# PGTNX08_pitch_out.net
KiCad netlist of a schematic drawn in EAGLE
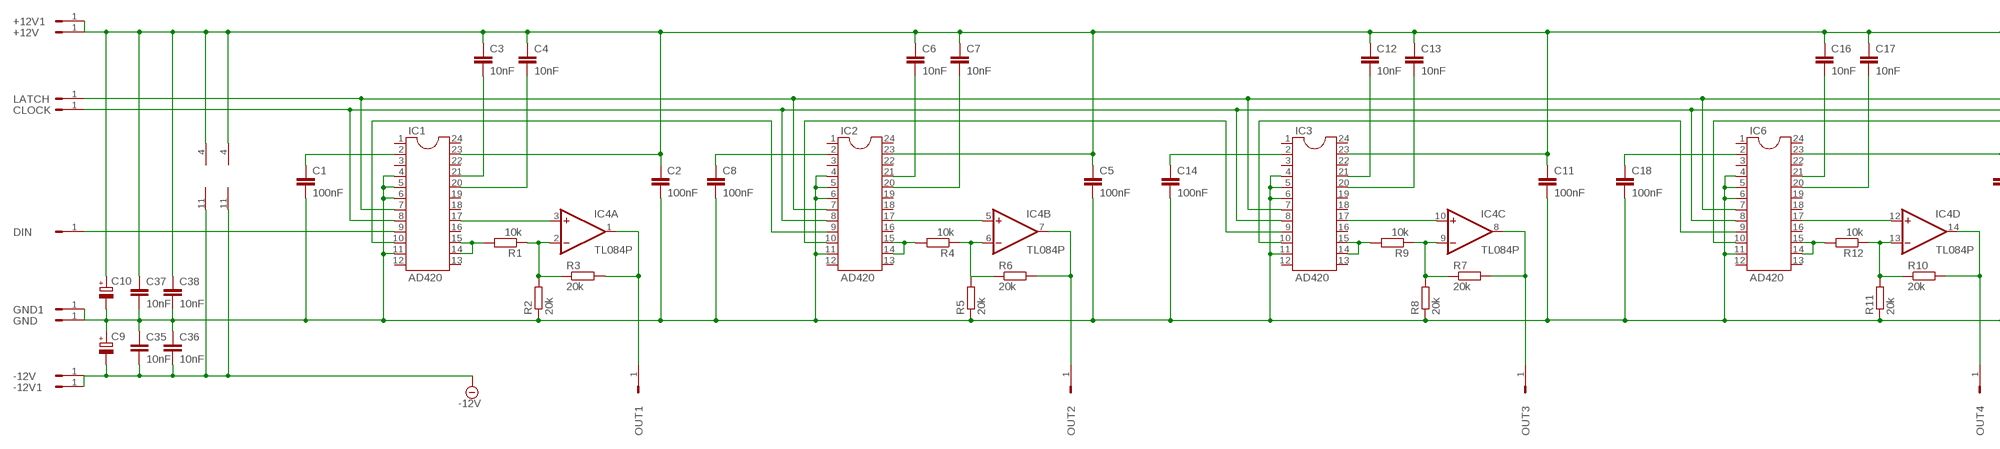
[diagram p0: schematic, sheet 1, part 1 of 2]
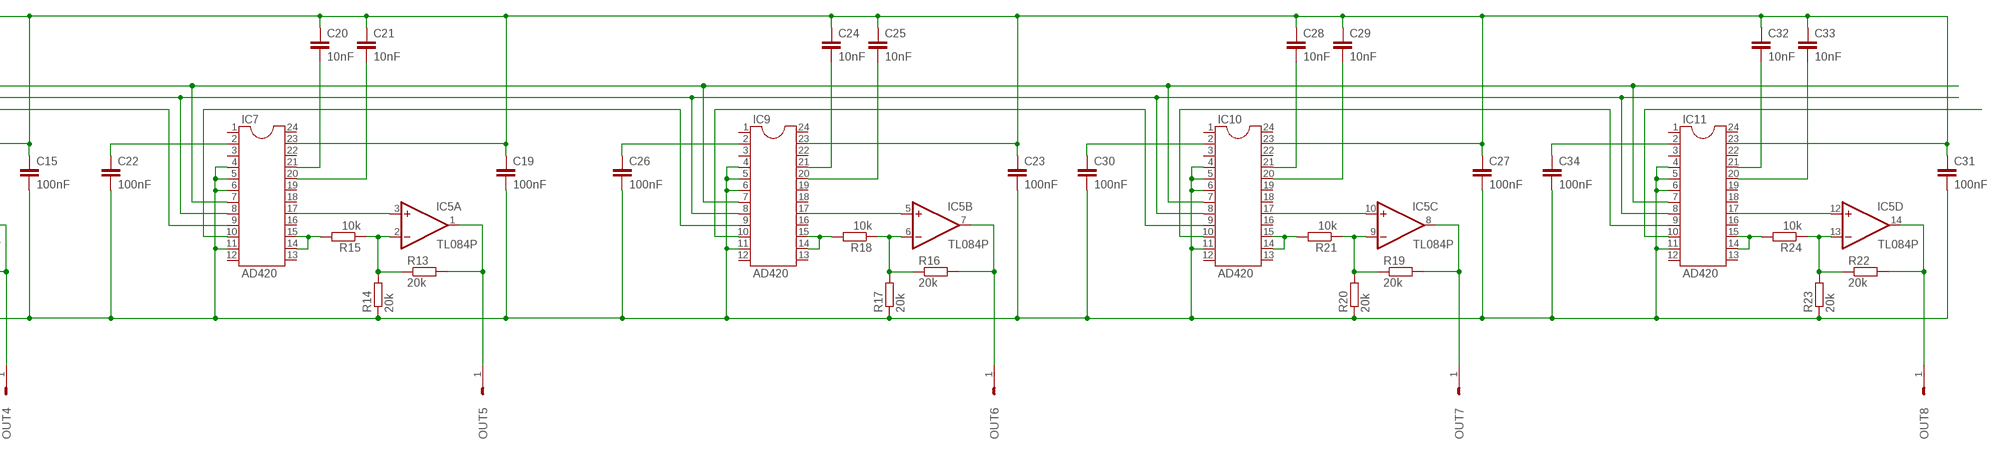
[diagram p1: schematic, sheet 1, part 2 of 2]

(export (version "E")
  (design (tool "Eeschema 10.0.6"))
  (components
    (comp (ref "+12V")
      (value "HEADER/MALE/01")
      (footprint "eagle-import:HEADER_MALE_01")
      (libsource (lib "eagle-import") (part "HEADER/MALE/01"))
    )
    (comp (ref "+12V1")
      (value "HEADER/MALE/01")
      (footprint "eagle-import:HEADER_MALE_01")
      (libsource (lib "eagle-import") (part "HEADER/MALE/01"))
    )
    (comp (ref "-12V")
      (value "HEADER/MALE/01")
      (footprint "eagle-import:HEADER_MALE_01")
      (libsource (lib "eagle-import") (part "HEADER/MALE/01"))
    )
    (comp (ref "-12V1")
      (value "HEADER/MALE/01")
      (footprint "eagle-import:HEADER_MALE_01")
      (libsource (lib "eagle-import") (part "HEADER/MALE/01"))
    )
    (comp (ref "C1")
      (value "100nF")
      (footprint "eagle-import:CERAMICDISC_5")
      (libsource (lib "eagle-import") (part "CAPACITORCERAMICDISC/5"))
    )
    (comp (ref "C2")
      (value "100nF")
      (footprint "eagle-import:CERAMICDISC_5")
      (libsource (lib "eagle-import") (part "CAPACITORCERAMICDISC/5"))
    )
    (comp (ref "C3")
      (value "10nF")
      (footprint "eagle-import:CERAMICDISC_5")
      (libsource (lib "eagle-import") (part "CAPACITORCERAMICDISC/5"))
    )
    (comp (ref "C4")
      (value "10nF")
      (footprint "eagle-import:CERAMICDISC_5")
      (libsource (lib "eagle-import") (part "CAPACITORCERAMICDISC/5"))
    )
    (comp (ref "C5")
      (value "100nF")
      (footprint "eagle-import:CERAMICDISC_5")
      (libsource (lib "eagle-import") (part "CAPACITORCERAMICDISC/5"))
    )
    (comp (ref "C6")
      (value "10nF")
      (footprint "eagle-import:CERAMICDISC_5")
      (libsource (lib "eagle-import") (part "CAPACITORCERAMICDISC/5"))
    )
    (comp (ref "C7")
      (value "10nF")
      (footprint "eagle-import:CERAMICDISC_5")
      (libsource (lib "eagle-import") (part "CAPACITORCERAMICDISC/5"))
    )
    (comp (ref "C8")
      (value "100nF")
      (footprint "eagle-import:CERAMICDISC_5")
      (libsource (lib "eagle-import") (part "CAPACITORCERAMICDISC/5"))
    )
    (comp (ref "C9")
      (value "CAPACITOR/POLARIZEDE2.5-6")
      (footprint "eagle-import:E2,5-6")
      (libsource (lib "eagle-import") (part "CAPACITOR/POLARIZEDE2.5-6"))
    )
    (comp (ref "C10")
      (value "CAPACITOR/POLARIZEDE2.5-6")
      (footprint "eagle-import:E2,5-6")
      (libsource (lib "eagle-import") (part "CAPACITOR/POLARIZEDE2.5-6"))
    )
    (comp (ref "C11")
      (value "100nF")
      (footprint "eagle-import:CERAMICDISC_5")
      (libsource (lib "eagle-import") (part "CAPACITORCERAMICDISC/5"))
    )
    (comp (ref "C12")
      (value "10nF")
      (footprint "eagle-import:CERAMICDISC_5")
      (libsource (lib "eagle-import") (part "CAPACITORCERAMICDISC/5"))
    )
    (comp (ref "C13")
      (value "10nF")
      (footprint "eagle-import:CERAMICDISC_5")
      (libsource (lib "eagle-import") (part "CAPACITORCERAMICDISC/5"))
    )
    (comp (ref "C14")
      (value "100nF")
      (footprint "eagle-import:CERAMICDISC_5")
      (libsource (lib "eagle-import") (part "CAPACITORCERAMICDISC/5"))
    )
    (comp (ref "C15")
      (value "100nF")
      (footprint "eagle-import:CERAMICDISC_5")
      (libsource (lib "eagle-import") (part "CAPACITORCERAMICDISC/5"))
    )
    (comp (ref "C16")
      (value "10nF")
      (footprint "eagle-import:CERAMICDISC_5")
      (libsource (lib "eagle-import") (part "CAPACITORCERAMICDISC/5"))
    )
    (comp (ref "C17")
      (value "10nF")
      (footprint "eagle-import:CERAMICDISC_5")
      (libsource (lib "eagle-import") (part "CAPACITORCERAMICDISC/5"))
    )
    (comp (ref "C18")
      (value "100nF")
      (footprint "eagle-import:CERAMICDISC_5")
      (libsource (lib "eagle-import") (part "CAPACITORCERAMICDISC/5"))
    )
    (comp (ref "C19")
      (value "100nF")
      (footprint "eagle-import:CERAMICDISC_5")
      (libsource (lib "eagle-import") (part "CAPACITORCERAMICDISC/5"))
    )
    (comp (ref "C20")
      (value "10nF")
      (footprint "eagle-import:CERAMICDISC_5")
      (libsource (lib "eagle-import") (part "CAPACITORCERAMICDISC/5"))
    )
    (comp (ref "C21")
      (value "10nF")
      (footprint "eagle-import:CERAMICDISC_5")
      (libsource (lib "eagle-import") (part "CAPACITORCERAMICDISC/5"))
    )
    (comp (ref "C22")
      (value "100nF")
      (footprint "eagle-import:CERAMICDISC_5")
      (libsource (lib "eagle-import") (part "CAPACITORCERAMICDISC/5"))
    )
    (comp (ref "C23")
      (value "100nF")
      (footprint "eagle-import:CERAMICDISC_5")
      (libsource (lib "eagle-import") (part "CAPACITORCERAMICDISC/5"))
    )
    (comp (ref "C24")
      (value "10nF")
      (footprint "eagle-import:CERAMICDISC_5")
      (libsource (lib "eagle-import") (part "CAPACITORCERAMICDISC/5"))
    )
    (comp (ref "C25")
      (value "10nF")
      (footprint "eagle-import:CERAMICDISC_5")
      (libsource (lib "eagle-import") (part "CAPACITORCERAMICDISC/5"))
    )
    (comp (ref "C26")
      (value "100nF")
      (footprint "eagle-import:CERAMICDISC_5")
      (libsource (lib "eagle-import") (part "CAPACITORCERAMICDISC/5"))
    )
    (comp (ref "C27")
      (value "100nF")
      (footprint "eagle-import:CERAMICDISC_5")
      (libsource (lib "eagle-import") (part "CAPACITORCERAMICDISC/5"))
    )
    (comp (ref "C28")
      (value "10nF")
      (footprint "eagle-import:CERAMICDISC_5")
      (libsource (lib "eagle-import") (part "CAPACITORCERAMICDISC/5"))
    )
    (comp (ref "C29")
      (value "10nF")
      (footprint "eagle-import:CERAMICDISC_5")
      (libsource (lib "eagle-import") (part "CAPACITORCERAMICDISC/5"))
    )
    (comp (ref "C30")
      (value "100nF")
      (footprint "eagle-import:CERAMICDISC_5")
      (libsource (lib "eagle-import") (part "CAPACITORCERAMICDISC/5"))
    )
    (comp (ref "C31")
      (value "100nF")
      (footprint "eagle-import:CERAMICDISC_5")
      (libsource (lib "eagle-import") (part "CAPACITORCERAMICDISC/5"))
    )
    (comp (ref "C32")
      (value "10nF")
      (footprint "eagle-import:CERAMICDISC_5")
      (libsource (lib "eagle-import") (part "CAPACITORCERAMICDISC/5"))
    )
    (comp (ref "C33")
      (value "10nF")
      (footprint "eagle-import:CERAMICDISC_5")
      (libsource (lib "eagle-import") (part "CAPACITORCERAMICDISC/5"))
    )
    (comp (ref "C34")
      (value "100nF")
      (footprint "eagle-import:CERAMICDISC_5")
      (libsource (lib "eagle-import") (part "CAPACITORCERAMICDISC/5"))
    )
    (comp (ref "C35")
      (value "10nF")
      (footprint "eagle-import:CERAMICDISC_5")
      (libsource (lib "eagle-import") (part "CAPACITORCERAMICDISC/5"))
    )
    (comp (ref "C36")
      (value "10nF")
      (footprint "eagle-import:CERAMICDISC_5")
      (libsource (lib "eagle-import") (part "CAPACITORCERAMICDISC/5"))
    )
    (comp (ref "C37")
      (value "10nF")
      (footprint "eagle-import:CERAMICDISC_5")
      (libsource (lib "eagle-import") (part "CAPACITORCERAMICDISC/5"))
    )
    (comp (ref "C38")
      (value "10nF")
      (footprint "eagle-import:CERAMICDISC_5")
      (libsource (lib "eagle-import") (part "CAPACITORCERAMICDISC/5"))
    )
    (comp (ref "CLOCK")
      (value "HEADER/MALE/01")
      (footprint "eagle-import:HEADER_MALE_01")
      (libsource (lib "eagle-import") (part "HEADER/MALE/01"))
    )
    (comp (ref "DIN")
      (value "HEADER/MALE/01")
      (footprint "eagle-import:HEADER_MALE_01")
      (libsource (lib "eagle-import") (part "HEADER/MALE/01"))
    )
    (comp (ref "GND")
      (value "HEADER/MALE/01")
      (footprint "eagle-import:HEADER_MALE_01")
      (libsource (lib "eagle-import") (part "HEADER/MALE/01"))
    )
    (comp (ref "GND1")
      (value "HEADER/MALE/01")
      (footprint "eagle-import:HEADER_MALE_01")
      (libsource (lib "eagle-import") (part "HEADER/MALE/01"))
    )
    (comp (ref "IC1")
      (value "AD420")
      (footprint "eagle-import:DIL24-3")
      (libsource (lib "eagle-import") (part "DIL24-3"))
    )
    (comp (ref "IC2")
      (value "AD420")
      (footprint "eagle-import:DIL24-3")
      (libsource (lib "eagle-import") (part "DIL24-3"))
    )
    (comp (ref "IC3")
      (value "AD420")
      (footprint "eagle-import:DIL24-3")
      (libsource (lib "eagle-import") (part "DIL24-3"))
    )
    (comp (ref "IC4")
      (value "TL084P")
      (footprint "eagle-import:DIL14")
      (libsource (lib "eagle-import") (part "TL084P"))
    )
    (comp (ref "IC5")
      (value "TL084P")
      (footprint "eagle-import:DIL14")
      (libsource (lib "eagle-import") (part "TL084P"))
    )
    (comp (ref "IC6")
      (value "AD420")
      (footprint "eagle-import:DIL24-3")
      (libsource (lib "eagle-import") (part "DIL24-3"))
    )
    (comp (ref "IC7")
      (value "AD420")
      (footprint "eagle-import:DIL24-3")
      (libsource (lib "eagle-import") (part "DIL24-3"))
    )
    (comp (ref "IC9")
      (value "AD420")
      (footprint "eagle-import:DIL24-3")
      (libsource (lib "eagle-import") (part "DIL24-3"))
    )
    (comp (ref "IC10")
      (value "AD420")
      (footprint "eagle-import:DIL24-3")
      (libsource (lib "eagle-import") (part "DIL24-3"))
    )
    (comp (ref "IC11")
      (value "AD420")
      (footprint "eagle-import:DIL24-3")
      (libsource (lib "eagle-import") (part "DIL24-3"))
    )
    (comp (ref "LATCH")
      (value "HEADER/MALE/01")
      (footprint "eagle-import:HEADER_MALE_01")
      (libsource (lib "eagle-import") (part "HEADER/MALE/01"))
    )
    (comp (ref "OUT1")
      (value "HEADER/MALE/01")
      (footprint "eagle-import:HEADER_MALE_01")
      (libsource (lib "eagle-import") (part "HEADER/MALE/01"))
    )
    (comp (ref "OUT2")
      (value "HEADER/MALE/01")
      (footprint "eagle-import:HEADER_MALE_01")
      (libsource (lib "eagle-import") (part "HEADER/MALE/01"))
    )
    (comp (ref "OUT3")
      (value "HEADER/MALE/01")
      (footprint "eagle-import:HEADER_MALE_01")
      (libsource (lib "eagle-import") (part "HEADER/MALE/01"))
    )
    (comp (ref "OUT4")
      (value "HEADER/MALE/01")
      (footprint "eagle-import:HEADER_MALE_01")
      (libsource (lib "eagle-import") (part "HEADER/MALE/01"))
    )
    (comp (ref "OUT5")
      (value "HEADER/MALE/01")
      (footprint "eagle-import:HEADER_MALE_01")
      (libsource (lib "eagle-import") (part "HEADER/MALE/01"))
    )
    (comp (ref "OUT6")
      (value "HEADER/MALE/01")
      (footprint "eagle-import:HEADER_MALE_01")
      (libsource (lib "eagle-import") (part "HEADER/MALE/01"))
    )
    (comp (ref "OUT7")
      (value "HEADER/MALE/01")
      (footprint "eagle-import:HEADER_MALE_01")
      (libsource (lib "eagle-import") (part "HEADER/MALE/01"))
    )
    (comp (ref "OUT8")
      (value "HEADER/MALE/01")
      (footprint "eagle-import:HEADER_MALE_01")
      (libsource (lib "eagle-import") (part "HEADER/MALE/01"))
    )
    (comp (ref "R1")
      (value "10k")
      (footprint "eagle-import:0204_7")
      (libsource (lib "eagle-import") (part "R-EU_0204/7"))
    )
    (comp (ref "R2")
      (value "20k")
      (footprint "eagle-import:0204_7")
      (libsource (lib "eagle-import") (part "R-EU_0204/7"))
    )
    (comp (ref "R3")
      (value "20k")
      (footprint "eagle-import:RESISTOR_7.5")
      (libsource (lib "eagle-import") (part "RESISTORRESISTOR/UPRIGHT/7.5"))
    )
    (comp (ref "R4")
      (value "10k")
      (footprint "eagle-import:0204_7")
      (libsource (lib "eagle-import") (part "R-EU_0204/7"))
    )
    (comp (ref "R5")
      (value "20k")
      (footprint "eagle-import:0204_7")
      (libsource (lib "eagle-import") (part "R-EU_0204/7"))
    )
    (comp (ref "R6")
      (value "20k")
      (footprint "eagle-import:RESISTOR_7.5")
      (libsource (lib "eagle-import") (part "RESISTORRESISTOR/UPRIGHT/7.5"))
    )
    (comp (ref "R7")
      (value "20k")
      (footprint "eagle-import:RESISTOR_7.5")
      (libsource (lib "eagle-import") (part "RESISTORRESISTOR/UPRIGHT/7.5"))
    )
    (comp (ref "R8")
      (value "20k")
      (footprint "eagle-import:RESISTOR_7.5")
      (libsource (lib "eagle-import") (part "RESISTORRESISTOR/UPRIGHT/7.5"))
    )
    (comp (ref "R9")
      (value "10k")
      (footprint "eagle-import:RESISTOR_7.5")
      (libsource (lib "eagle-import") (part "RESISTORRESISTOR/UPRIGHT/7.5"))
    )
    (comp (ref "R10")
      (value "20k")
      (footprint "eagle-import:RESISTOR_7.5")
      (libsource (lib "eagle-import") (part "RESISTORRESISTOR/UPRIGHT/7.5"))
    )
    (comp (ref "R11")
      (value "20k")
      (footprint "eagle-import:RESISTOR_7.5")
      (libsource (lib "eagle-import") (part "RESISTORRESISTOR/UPRIGHT/7.5"))
    )
    (comp (ref "R12")
      (value "10k")
      (footprint "eagle-import:RESISTOR_7.5")
      (libsource (lib "eagle-import") (part "RESISTORRESISTOR/UPRIGHT/7.5"))
    )
    (comp (ref "R13")
      (value "20k")
      (footprint "eagle-import:RESISTOR_7.5")
      (libsource (lib "eagle-import") (part "RESISTORRESISTOR/UPRIGHT/7.5"))
    )
    (comp (ref "R14")
      (value "20k")
      (footprint "eagle-import:RESISTOR_7.5")
      (libsource (lib "eagle-import") (part "RESISTORRESISTOR/UPRIGHT/7.5"))
    )
    (comp (ref "R15")
      (value "10k")
      (footprint "eagle-import:RESISTOR_7.5")
      (libsource (lib "eagle-import") (part "RESISTORRESISTOR/UPRIGHT/7.5"))
    )
    (comp (ref "R16")
      (value "20k")
      (footprint "eagle-import:RESISTOR_7.5")
      (libsource (lib "eagle-import") (part "RESISTORRESISTOR/UPRIGHT/7.5"))
    )
    (comp (ref "R17")
      (value "20k")
      (footprint "eagle-import:RESISTOR_7.5")
      (libsource (lib "eagle-import") (part "RESISTORRESISTOR/UPRIGHT/7.5"))
    )
    (comp (ref "R18")
      (value "10k")
      (footprint "eagle-import:RESISTOR_7.5")
      (libsource (lib "eagle-import") (part "RESISTORRESISTOR/UPRIGHT/7.5"))
    )
    (comp (ref "R19")
      (value "20k")
      (footprint "eagle-import:RESISTOR_7.5")
      (libsource (lib "eagle-import") (part "RESISTORRESISTOR/UPRIGHT/7.5"))
    )
    (comp (ref "R20")
      (value "20k")
      (footprint "eagle-import:RESISTOR_7.5")
      (libsource (lib "eagle-import") (part "RESISTORRESISTOR/UPRIGHT/7.5"))
    )
    (comp (ref "R21")
      (value "10k")
      (footprint "eagle-import:RESISTOR_7.5")
      (libsource (lib "eagle-import") (part "RESISTORRESISTOR/UPRIGHT/7.5"))
    )
    (comp (ref "R22")
      (value "20k")
      (footprint "eagle-import:RESISTOR_7.5")
      (libsource (lib "eagle-import") (part "RESISTORRESISTOR/UPRIGHT/7.5"))
    )
    (comp (ref "R23")
      (value "20k")
      (footprint "eagle-import:RESISTOR_7.5")
      (libsource (lib "eagle-import") (part "RESISTORRESISTOR/UPRIGHT/7.5"))
    )
    (comp (ref "R24")
      (value "10k")
      (footprint "eagle-import:RESISTOR_7.5")
      (libsource (lib "eagle-import") (part "RESISTORRESISTOR/UPRIGHT/7.5"))
    )
  )
  (nets
    (net (code "1") (name "-12V") (class "Default")
      (node (ref "-12V") (pin "1") (pinfunction "3_1") (pintype "passive"))
      (node (ref "-12V1") (pin "1") (pinfunction "3_1") (pintype "passive"))
      (node (ref "C35") (pin "2") (pinfunction "2_2") (pintype "passive"))
      (node (ref "C36") (pin "2") (pinfunction "2_2") (pintype "passive"))
      (node (ref "C9") (pin "-") (pinfunction "-_-") (pintype "passive"))
      (node (ref "IC4") (pin "11") (pinfunction "V-_11") (pintype "power_in"))
      (node (ref "IC5") (pin "11") (pinfunction "V-_11") (pintype "power_in"))
    )
    (net (code "2") (name "Net-(+12V-3)") (class "Default")
      (node (ref "+12V") (pin "1") (pinfunction "3_1") (pintype "passive"))
      (node (ref "+12V1") (pin "1") (pinfunction "3_1") (pintype "passive"))
      (node (ref "C10") (pin "+") (pinfunction "+_+") (pintype "passive"))
      (node (ref "C11") (pin "1") (pinfunction "1_1") (pintype "passive"))
      (node (ref "C12") (pin "1") (pinfunction "1_1") (pintype "passive"))
      (node (ref "C13") (pin "1") (pinfunction "1_1") (pintype "passive"))
      (node (ref "C15") (pin "1") (pinfunction "1_1") (pintype "passive"))
      (node (ref "C16") (pin "1") (pinfunction "1_1") (pintype "passive"))
      (node (ref "C17") (pin "1") (pinfunction "1_1") (pintype "passive"))
      (node (ref "C19") (pin "1") (pinfunction "1_1") (pintype "passive"))
      (node (ref "C2") (pin "1") (pinfunction "1_1") (pintype "passive"))
      (node (ref "C20") (pin "1") (pinfunction "1_1") (pintype "passive"))
      (node (ref "C21") (pin "1") (pinfunction "1_1") (pintype "passive"))
      (node (ref "C23") (pin "1") (pinfunction "1_1") (pintype "passive"))
      (node (ref "C24") (pin "1") (pinfunction "1_1") (pintype "passive"))
      (node (ref "C25") (pin "1") (pinfunction "1_1") (pintype "passive"))
      (node (ref "C27") (pin "1") (pinfunction "1_1") (pintype "passive"))
      (node (ref "C28") (pin "1") (pinfunction "1_1") (pintype "passive"))
      (node (ref "C29") (pin "1") (pinfunction "1_1") (pintype "passive"))
      (node (ref "C3") (pin "1") (pinfunction "1_1") (pintype "passive"))
      (node (ref "C31") (pin "1") (pinfunction "1_1") (pintype "passive"))
      (node (ref "C32") (pin "1") (pinfunction "1_1") (pintype "passive"))
      (node (ref "C33") (pin "1") (pinfunction "1_1") (pintype "passive"))
      (node (ref "C37") (pin "1") (pinfunction "1_1") (pintype "passive"))
      (node (ref "C38") (pin "1") (pinfunction "1_1") (pintype "passive"))
      (node (ref "C4") (pin "1") (pinfunction "1_1") (pintype "passive"))
      (node (ref "C5") (pin "1") (pinfunction "1_1") (pintype "passive"))
      (node (ref "C6") (pin "1") (pinfunction "1_1") (pintype "passive"))
      (node (ref "C7") (pin "1") (pinfunction "1_1") (pintype "passive"))
      (node (ref "IC1") (pin "23") (pinfunction "23_23") (pintype "passive"))
      (node (ref "IC10") (pin "23") (pinfunction "23_23") (pintype "passive"))
      (node (ref "IC11") (pin "23") (pinfunction "23_23") (pintype "passive"))
      (node (ref "IC2") (pin "23") (pinfunction "23_23") (pintype "passive"))
      (node (ref "IC3") (pin "23") (pinfunction "23_23") (pintype "passive"))
      (node (ref "IC4") (pin "4") (pinfunction "V+_4") (pintype "power_in"))
      (node (ref "IC5") (pin "4") (pinfunction "V+_4") (pintype "power_in"))
      (node (ref "IC6") (pin "23") (pinfunction "23_23") (pintype "passive"))
      (node (ref "IC7") (pin "23") (pinfunction "23_23") (pintype "passive"))
      (node (ref "IC9") (pin "23") (pinfunction "23_23") (pintype "passive"))
    )
    (net (code "3") (name "Net-(C1-Pad1)") (class "Default")
      (node (ref "C1") (pin "1") (pinfunction "1_1") (pintype "passive"))
      (node (ref "IC1") (pin "2") (pinfunction "2_2") (pintype "passive"))
    )
    (net (code "4") (name "Net-(C3-Pad2)") (class "Default")
      (node (ref "C3") (pin "2") (pinfunction "2_2") (pintype "passive"))
      (node (ref "IC1") (pin "21") (pinfunction "21_21") (pintype "passive"))
    )
    (net (code "5") (name "Net-(C4-Pad2)") (class "Default")
      (node (ref "C4") (pin "2") (pinfunction "2_2") (pintype "passive"))
      (node (ref "IC1") (pin "20") (pinfunction "20_20") (pintype "passive"))
    )
    (net (code "6") (name "Net-(C6-Pad2)") (class "Default")
      (node (ref "C6") (pin "2") (pinfunction "2_2") (pintype "passive"))
      (node (ref "IC2") (pin "21") (pinfunction "21_21") (pintype "passive"))
    )
    (net (code "7") (name "Net-(C7-Pad2)") (class "Default")
      (node (ref "C7") (pin "2") (pinfunction "2_2") (pintype "passive"))
      (node (ref "IC2") (pin "20") (pinfunction "20_20") (pintype "passive"))
    )
    (net (code "8") (name "Net-(C8-Pad1)") (class "Default")
      (node (ref "C8") (pin "1") (pinfunction "1_1") (pintype "passive"))
      (node (ref "IC2") (pin "2") (pinfunction "2_2") (pintype "passive"))
    )
    (net (code "9") (name "Net-(C12-Pad2)") (class "Default")
      (node (ref "C12") (pin "2") (pinfunction "2_2") (pintype "passive"))
      (node (ref "IC3") (pin "21") (pinfunction "21_21") (pintype "passive"))
    )
    (net (code "10") (name "Net-(C13-Pad2)") (class "Default")
      (node (ref "C13") (pin "2") (pinfunction "2_2") (pintype "passive"))
      (node (ref "IC3") (pin "20") (pinfunction "20_20") (pintype "passive"))
    )
    (net (code "11") (name "Net-(C14-Pad1)") (class "Default")
      (node (ref "C14") (pin "1") (pinfunction "1_1") (pintype "passive"))
      (node (ref "IC3") (pin "2") (pinfunction "2_2") (pintype "passive"))
    )
    (net (code "12") (name "Net-(C16-Pad2)") (class "Default")
      (node (ref "C16") (pin "2") (pinfunction "2_2") (pintype "passive"))
      (node (ref "IC6") (pin "21") (pinfunction "21_21") (pintype "passive"))
    )
    (net (code "13") (name "Net-(C17-Pad2)") (class "Default")
      (node (ref "C17") (pin "2") (pinfunction "2_2") (pintype "passive"))
      (node (ref "IC6") (pin "20") (pinfunction "20_20") (pintype "passive"))
    )
    (net (code "14") (name "Net-(C18-Pad1)") (class "Default")
      (node (ref "C18") (pin "1") (pinfunction "1_1") (pintype "passive"))
      (node (ref "IC6") (pin "2") (pinfunction "2_2") (pintype "passive"))
    )
    (net (code "15") (name "Net-(C20-Pad2)") (class "Default")
      (node (ref "C20") (pin "2") (pinfunction "2_2") (pintype "passive"))
      (node (ref "IC7") (pin "21") (pinfunction "21_21") (pintype "passive"))
    )
    (net (code "16") (name "Net-(C21-Pad2)") (class "Default")
      (node (ref "C21") (pin "2") (pinfunction "2_2") (pintype "passive"))
      (node (ref "IC7") (pin "20") (pinfunction "20_20") (pintype "passive"))
    )
    (net (code "17") (name "Net-(C22-Pad1)") (class "Default")
      (node (ref "C22") (pin "1") (pinfunction "1_1") (pintype "passive"))
      (node (ref "IC7") (pin "2") (pinfunction "2_2") (pintype "passive"))
    )
    (net (code "18") (name "Net-(C24-Pad2)") (class "Default")
      (node (ref "C24") (pin "2") (pinfunction "2_2") (pintype "passive"))
      (node (ref "IC9") (pin "21") (pinfunction "21_21") (pintype "passive"))
    )
    (net (code "19") (name "Net-(C25-Pad2)") (class "Default")
      (node (ref "C25") (pin "2") (pinfunction "2_2") (pintype "passive"))
      (node (ref "IC9") (pin "20") (pinfunction "20_20") (pintype "passive"))
    )
    (net (code "20") (name "Net-(C26-Pad1)") (class "Default")
      (node (ref "C26") (pin "1") (pinfunction "1_1") (pintype "passive"))
      (node (ref "IC9") (pin "2") (pinfunction "2_2") (pintype "passive"))
    )
    (net (code "21") (name "Net-(C28-Pad2)") (class "Default")
      (node (ref "C28") (pin "2") (pinfunction "2_2") (pintype "passive"))
      (node (ref "IC10") (pin "21") (pinfunction "21_21") (pintype "passive"))
    )
    (net (code "22") (name "Net-(C29-Pad2)") (class "Default")
      (node (ref "C29") (pin "2") (pinfunction "2_2") (pintype "passive"))
      (node (ref "IC10") (pin "20") (pinfunction "20_20") (pintype "passive"))
    )
    (net (code "23") (name "Net-(C30-Pad1)") (class "Default")
      (node (ref "C30") (pin "1") (pinfunction "1_1") (pintype "passive"))
      (node (ref "IC10") (pin "2") (pinfunction "2_2") (pintype "passive"))
    )
    (net (code "24") (name "Net-(C32-Pad2)") (class "Default")
      (node (ref "C32") (pin "2") (pinfunction "2_2") (pintype "passive"))
      (node (ref "IC11") (pin "21") (pinfunction "21_21") (pintype "passive"))
    )
    (net (code "25") (name "Net-(C33-Pad2)") (class "Default")
      (node (ref "C33") (pin "2") (pinfunction "2_2") (pintype "passive"))
      (node (ref "IC11") (pin "20") (pinfunction "20_20") (pintype "passive"))
    )
    (net (code "26") (name "Net-(C34-Pad1)") (class "Default")
      (node (ref "C34") (pin "1") (pinfunction "1_1") (pintype "passive"))
      (node (ref "IC11") (pin "2") (pinfunction "2_2") (pintype "passive"))
    )
    (net (code "27") (name "Net-(CLOCK-3)") (class "Default")
      (node (ref "CLOCK") (pin "1") (pinfunction "3_1") (pintype "passive"))
      (node (ref "IC1") (pin "8") (pinfunction "8_8") (pintype "passive"))
      (node (ref "IC10") (pin "8") (pinfunction "8_8") (pintype "passive"))
      (node (ref "IC11") (pin "8") (pinfunction "8_8") (pintype "passive"))
      (node (ref "IC2") (pin "8") (pinfunction "8_8") (pintype "passive"))
      (node (ref "IC3") (pin "8") (pinfunction "8_8") (pintype "passive"))
      (node (ref "IC6") (pin "8") (pinfunction "8_8") (pintype "passive"))
      (node (ref "IC7") (pin "8") (pinfunction "8_8") (pintype "passive"))
      (node (ref "IC9") (pin "8") (pinfunction "8_8") (pintype "passive"))
    )
    (net (code "28") (name "Net-(DIN-3)") (class "Default")
      (node (ref "DIN") (pin "1") (pinfunction "3_1") (pintype "passive"))
      (node (ref "IC1") (pin "9") (pinfunction "9_9") (pintype "passive"))
    )
    (net (code "29") (name "Net-(GND-3)") (class "Default")
      (node (ref "C1") (pin "2") (pinfunction "2_2") (pintype "passive"))
      (node (ref "C10") (pin "-") (pinfunction "-_-") (pintype "passive"))
      (node (ref "C11") (pin "2") (pinfunction "2_2") (pintype "passive"))
      (node (ref "C14") (pin "2") (pinfunction "2_2") (pintype "passive"))
      (node (ref "C15") (pin "2") (pinfunction "2_2") (pintype "passive"))
      (node (ref "C18") (pin "2") (pinfunction "2_2") (pintype "passive"))
      (node (ref "C19") (pin "2") (pinfunction "2_2") (pintype "passive"))
      (node (ref "C2") (pin "2") (pinfunction "2_2") (pintype "passive"))
      (node (ref "C22") (pin "2") (pinfunction "2_2") (pintype "passive"))
      (node (ref "C23") (pin "2") (pinfunction "2_2") (pintype "passive"))
      (node (ref "C26") (pin "2") (pinfunction "2_2") (pintype "passive"))
      (node (ref "C27") (pin "2") (pinfunction "2_2") (pintype "passive"))
      (node (ref "C30") (pin "2") (pinfunction "2_2") (pintype "passive"))
      (node (ref "C31") (pin "2") (pinfunction "2_2") (pintype "passive"))
      (node (ref "C34") (pin "2") (pinfunction "2_2") (pintype "passive"))
      (node (ref "C35") (pin "1") (pinfunction "1_1") (pintype "passive"))
      (node (ref "C36") (pin "1") (pinfunction "1_1") (pintype "passive"))
      (node (ref "C37") (pin "2") (pinfunction "2_2") (pintype "passive"))
      (node (ref "C38") (pin "2") (pinfunction "2_2") (pintype "passive"))
      (node (ref "C5") (pin "2") (pinfunction "2_2") (pintype "passive"))
      (node (ref "C8") (pin "2") (pinfunction "2_2") (pintype "passive"))
      (node (ref "C9") (pin "+") (pinfunction "+_+") (pintype "passive"))
      (node (ref "GND") (pin "1") (pinfunction "3_1") (pintype "passive"))
      (node (ref "GND1") (pin "1") (pinfunction "3_1") (pintype "passive"))
      (node (ref "IC1") (pin "11") (pinfunction "11_11") (pintype "passive"))
      (node (ref "IC1") (pin "4") (pinfunction "4_4") (pintype "passive"))
      (node (ref "IC1") (pin "5") (pinfunction "5_5") (pintype "passive"))
      (node (ref "IC1") (pin "6") (pinfunction "6_6") (pintype "passive"))
      (node (ref "IC10") (pin "11") (pinfunction "11_11") (pintype "passive"))
      (node (ref "IC10") (pin "4") (pinfunction "4_4") (pintype "passive"))
      (node (ref "IC10") (pin "5") (pinfunction "5_5") (pintype "passive"))
      (node (ref "IC10") (pin "6") (pinfunction "6_6") (pintype "passive"))
      (node (ref "IC11") (pin "11") (pinfunction "11_11") (pintype "passive"))
      (node (ref "IC11") (pin "4") (pinfunction "4_4") (pintype "passive"))
      (node (ref "IC11") (pin "5") (pinfunction "5_5") (pintype "passive"))
      (node (ref "IC11") (pin "6") (pinfunction "6_6") (pintype "passive"))
      (node (ref "IC2") (pin "11") (pinfunction "11_11") (pintype "passive"))
      (node (ref "IC2") (pin "4") (pinfunction "4_4") (pintype "passive"))
      (node (ref "IC2") (pin "5") (pinfunction "5_5") (pintype "passive"))
      (node (ref "IC2") (pin "6") (pinfunction "6_6") (pintype "passive"))
      (node (ref "IC3") (pin "11") (pinfunction "11_11") (pintype "passive"))
      (node (ref "IC3") (pin "4") (pinfunction "4_4") (pintype "passive"))
      (node (ref "IC3") (pin "5") (pinfunction "5_5") (pintype "passive"))
      (node (ref "IC3") (pin "6") (pinfunction "6_6") (pintype "passive"))
      (node (ref "IC6") (pin "11") (pinfunction "11_11") (pintype "passive"))
      (node (ref "IC6") (pin "4") (pinfunction "4_4") (pintype "passive"))
      (node (ref "IC6") (pin "5") (pinfunction "5_5") (pintype "passive"))
      (node (ref "IC6") (pin "6") (pinfunction "6_6") (pintype "passive"))
      (node (ref "IC7") (pin "11") (pinfunction "11_11") (pintype "passive"))
      (node (ref "IC7") (pin "4") (pinfunction "4_4") (pintype "passive"))
      (node (ref "IC7") (pin "5") (pinfunction "5_5") (pintype "passive"))
      (node (ref "IC7") (pin "6") (pinfunction "6_6") (pintype "passive"))
      (node (ref "IC9") (pin "11") (pinfunction "11_11") (pintype "passive"))
      (node (ref "IC9") (pin "4") (pinfunction "4_4") (pintype "passive"))
      (node (ref "IC9") (pin "5") (pinfunction "5_5") (pintype "passive"))
      (node (ref "IC9") (pin "6") (pinfunction "6_6") (pintype "passive"))
      (node (ref "R11") (pin "1") (pinfunction "1_1") (pintype "passive"))
      (node (ref "R14") (pin "1") (pinfunction "1_1") (pintype "passive"))
      (node (ref "R17") (pin "1") (pinfunction "1_1") (pintype "passive"))
      (node (ref "R2") (pin "1") (pinfunction "1_1") (pintype "passive"))
      (node (ref "R20") (pin "1") (pinfunction "1_1") (pintype "passive"))
      (node (ref "R23") (pin "1") (pinfunction "1_1") (pintype "passive"))
      (node (ref "R5") (pin "1") (pinfunction "1_1") (pintype "passive"))
      (node (ref "R8") (pin "1") (pinfunction "1_1") (pintype "passive"))
    )
    (net (code "30") (name "Net-(IC1-Pad10)") (class "Default")
      (node (ref "IC1") (pin "10") (pinfunction "10_10") (pintype "passive"))
      (node (ref "IC2") (pin "9") (pinfunction "9_9") (pintype "passive"))
    )
    (net (code "31") (name "Net-(IC1-Pad14)") (class "Default")
      (node (ref "IC1") (pin "14") (pinfunction "14_14") (pintype "passive"))
      (node (ref "IC1") (pin "15") (pinfunction "15_15") (pintype "passive"))
      (node (ref "R1") (pin "2") (pinfunction "2_2") (pintype "passive"))
    )
    (net (code "32") (name "Net-(IC2-Pad10)") (class "Default")
      (node (ref "IC2") (pin "10") (pinfunction "10_10") (pintype "passive"))
      (node (ref "IC3") (pin "9") (pinfunction "9_9") (pintype "passive"))
    )
    (net (code "33") (name "Net-(IC2-Pad14)") (class "Default")
      (node (ref "IC2") (pin "14") (pinfunction "14_14") (pintype "passive"))
      (node (ref "IC2") (pin "15") (pinfunction "15_15") (pintype "passive"))
      (node (ref "R4") (pin "2") (pinfunction "2_2") (pintype "passive"))
    )
    (net (code "34") (name "Net-(IC3-Pad10)") (class "Default")
      (node (ref "IC3") (pin "10") (pinfunction "10_10") (pintype "passive"))
      (node (ref "IC6") (pin "9") (pinfunction "9_9") (pintype "passive"))
    )
    (net (code "35") (name "Net-(IC3-Pad14)") (class "Default")
      (node (ref "IC3") (pin "14") (pinfunction "14_14") (pintype "passive"))
      (node (ref "IC3") (pin "15") (pinfunction "15_15") (pintype "passive"))
      (node (ref "R9") (pin "2") (pinfunction "2_2") (pintype "passive"))
    )
    (net (code "36") (name "Net-(IC4A-+IN)") (class "Default")
      (node (ref "IC1") (pin "17") (pinfunction "17_17") (pintype "passive"))
      (node (ref "IC4") (pin "3") (pinfunction "+IN_3") (pintype "input"))
    )
    (net (code "37") (name "Net-(IC4A--IN)") (class "Default")
      (node (ref "IC4") (pin "2") (pinfunction "-IN_2") (pintype "input"))
      (node (ref "R1") (pin "1") (pinfunction "1_1") (pintype "passive"))
      (node (ref "R2") (pin "2") (pinfunction "2_2") (pintype "passive"))
      (node (ref "R3") (pin "1") (pinfunction "1_1") (pintype "passive"))
    )
    (net (code "38") (name "Net-(IC4A-OUT)") (class "Default")
      (node (ref "IC4") (pin "1") (pinfunction "OUT_1") (pintype "output"))
      (node (ref "OUT1") (pin "1") (pinfunction "3_1") (pintype "passive"))
      (node (ref "R3") (pin "2") (pinfunction "2_2") (pintype "passive"))
    )
    (net (code "39") (name "Net-(IC4B-+IN)") (class "Default")
      (node (ref "IC2") (pin "17") (pinfunction "17_17") (pintype "passive"))
      (node (ref "IC4") (pin "5") (pinfunction "+IN_5") (pintype "input"))
    )
    (net (code "40") (name "Net-(IC4B--IN)") (class "Default")
      (node (ref "IC4") (pin "6") (pinfunction "-IN_6") (pintype "input"))
      (node (ref "R4") (pin "1") (pinfunction "1_1") (pintype "passive"))
      (node (ref "R5") (pin "2") (pinfunction "2_2") (pintype "passive"))
      (node (ref "R6") (pin "1") (pinfunction "1_1") (pintype "passive"))
    )
    (net (code "41") (name "Net-(IC4B-OUT)") (class "Default")
      (node (ref "IC4") (pin "7") (pinfunction "OUT_7") (pintype "output"))
      (node (ref "OUT2") (pin "1") (pinfunction "3_1") (pintype "passive"))
      (node (ref "R6") (pin "2") (pinfunction "2_2") (pintype "passive"))
    )
    (net (code "42") (name "Net-(IC4C-+IN)") (class "Default")
      (node (ref "IC3") (pin "17") (pinfunction "17_17") (pintype "passive"))
      (node (ref "IC4") (pin "10") (pinfunction "+IN_10") (pintype "input"))
    )
    (net (code "43") (name "Net-(IC4C--IN)") (class "Default")
      (node (ref "IC4") (pin "9") (pinfunction "-IN_9") (pintype "input"))
      (node (ref "R7") (pin "1") (pinfunction "1_1") (pintype "passive"))
      (node (ref "R8") (pin "2") (pinfunction "2_2") (pintype "passive"))
      (node (ref "R9") (pin "1") (pinfunction "1_1") (pintype "passive"))
    )
    (net (code "44") (name "Net-(IC4C-OUT)") (class "Default")
      (node (ref "IC4") (pin "8") (pinfunction "OUT_8") (pintype "output"))
      (node (ref "OUT3") (pin "1") (pinfunction "3_1") (pintype "passive"))
      (node (ref "R7") (pin "2") (pinfunction "2_2") (pintype "passive"))
    )
    (net (code "45") (name "Net-(IC4D-+IN)") (class "Default")
      (node (ref "IC4") (pin "12") (pinfunction "+IN_12") (pintype "input"))
      (node (ref "IC6") (pin "17") (pinfunction "17_17") (pintype "passive"))
    )
    (net (code "46") (name "Net-(IC4D--IN)") (class "Default")
      (node (ref "IC4") (pin "13") (pinfunction "-IN_13") (pintype "input"))
      (node (ref "R10") (pin "1") (pinfunction "1_1") (pintype "passive"))
      (node (ref "R11") (pin "2") (pinfunction "2_2") (pintype "passive"))
      (node (ref "R12") (pin "1") (pinfunction "1_1") (pintype "passive"))
    )
    (net (code "47") (name "Net-(IC4D-OUT)") (class "Default")
      (node (ref "IC4") (pin "14") (pinfunction "OUT_14") (pintype "output"))
      (node (ref "OUT4") (pin "1") (pinfunction "3_1") (pintype "passive"))
      (node (ref "R10") (pin "2") (pinfunction "2_2") (pintype "passive"))
    )
    (net (code "48") (name "Net-(IC5A-+IN)") (class "Default")
      (node (ref "IC5") (pin "3") (pinfunction "+IN_3") (pintype "input"))
      (node (ref "IC7") (pin "17") (pinfunction "17_17") (pintype "passive"))
    )
    (net (code "49") (name "Net-(IC5A--IN)") (class "Default")
      (node (ref "IC5") (pin "2") (pinfunction "-IN_2") (pintype "input"))
      (node (ref "R13") (pin "1") (pinfunction "1_1") (pintype "passive"))
      (node (ref "R14") (pin "2") (pinfunction "2_2") (pintype "passive"))
      (node (ref "R15") (pin "1") (pinfunction "1_1") (pintype "passive"))
    )
    (net (code "50") (name "Net-(IC5A-OUT)") (class "Default")
      (node (ref "IC5") (pin "1") (pinfunction "OUT_1") (pintype "output"))
      (node (ref "OUT5") (pin "1") (pinfunction "3_1") (pintype "passive"))
      (node (ref "R13") (pin "2") (pinfunction "2_2") (pintype "passive"))
    )
    (net (code "51") (name "Net-(IC5B-+IN)") (class "Default")
      (node (ref "IC5") (pin "5") (pinfunction "+IN_5") (pintype "input"))
      (node (ref "IC9") (pin "17") (pinfunction "17_17") (pintype "passive"))
    )
    (net (code "52") (name "Net-(IC5B--IN)") (class "Default")
      (node (ref "IC5") (pin "6") (pinfunction "-IN_6") (pintype "input"))
      (node (ref "R16") (pin "1") (pinfunction "1_1") (pintype "passive"))
      (node (ref "R17") (pin "2") (pinfunction "2_2") (pintype "passive"))
      (node (ref "R18") (pin "1") (pinfunction "1_1") (pintype "passive"))
    )
    (net (code "53") (name "Net-(IC5B-OUT)") (class "Default")
      (node (ref "IC5") (pin "7") (pinfunction "OUT_7") (pintype "output"))
      (node (ref "OUT6") (pin "1") (pinfunction "3_1") (pintype "passive"))
      (node (ref "R16") (pin "2") (pinfunction "2_2") (pintype "passive"))
    )
    (net (code "54") (name "Net-(IC5C-+IN)") (class "Default")
      (node (ref "IC10") (pin "17") (pinfunction "17_17") (pintype "passive"))
      (node (ref "IC5") (pin "10") (pinfunction "+IN_10") (pintype "input"))
    )
    (net (code "55") (name "Net-(IC5C--IN)") (class "Default")
      (node (ref "IC5") (pin "9") (pinfunction "-IN_9") (pintype "input"))
      (node (ref "R19") (pin "1") (pinfunction "1_1") (pintype "passive"))
      (node (ref "R20") (pin "2") (pinfunction "2_2") (pintype "passive"))
      (node (ref "R21") (pin "1") (pinfunction "1_1") (pintype "passive"))
    )
    (net (code "56") (name "Net-(IC5C-OUT)") (class "Default")
      (node (ref "IC5") (pin "8") (pinfunction "OUT_8") (pintype "output"))
      (node (ref "OUT7") (pin "1") (pinfunction "3_1") (pintype "passive"))
      (node (ref "R19") (pin "2") (pinfunction "2_2") (pintype "passive"))
    )
    (net (code "57") (name "Net-(IC5D-+IN)") (class "Default")
      (node (ref "IC11") (pin "17") (pinfunction "17_17") (pintype "passive"))
      (node (ref "IC5") (pin "12") (pinfunction "+IN_12") (pintype "input"))
    )
    (net (code "58") (name "Net-(IC5D--IN)") (class "Default")
      (node (ref "IC5") (pin "13") (pinfunction "-IN_13") (pintype "input"))
      (node (ref "R22") (pin "1") (pinfunction "1_1") (pintype "passive"))
      (node (ref "R23") (pin "2") (pinfunction "2_2") (pintype "passive"))
      (node (ref "R24") (pin "1") (pinfunction "1_1") (pintype "passive"))
    )
    (net (code "59") (name "Net-(IC5D-OUT)") (class "Default")
      (node (ref "IC5") (pin "14") (pinfunction "OUT_14") (pintype "output"))
      (node (ref "OUT8") (pin "1") (pinfunction "3_1") (pintype "passive"))
      (node (ref "R22") (pin "2") (pinfunction "2_2") (pintype "passive"))
    )
    (net (code "60") (name "Net-(IC6-Pad10)") (class "Default")
      (node (ref "IC6") (pin "10") (pinfunction "10_10") (pintype "passive"))
      (node (ref "IC7") (pin "9") (pinfunction "9_9") (pintype "passive"))
    )
    (net (code "61") (name "Net-(IC6-Pad14)") (class "Default")
      (node (ref "IC6") (pin "14") (pinfunction "14_14") (pintype "passive"))
      (node (ref "IC6") (pin "15") (pinfunction "15_15") (pintype "passive"))
      (node (ref "R12") (pin "2") (pinfunction "2_2") (pintype "passive"))
    )
    (net (code "62") (name "Net-(IC7-Pad10)") (class "Default")
      (node (ref "IC7") (pin "10") (pinfunction "10_10") (pintype "passive"))
      (node (ref "IC9") (pin "9") (pinfunction "9_9") (pintype "passive"))
    )
    (net (code "63") (name "Net-(IC7-Pad14)") (class "Default")
      (node (ref "IC7") (pin "14") (pinfunction "14_14") (pintype "passive"))
      (node (ref "IC7") (pin "15") (pinfunction "15_15") (pintype "passive"))
      (node (ref "R15") (pin "2") (pinfunction "2_2") (pintype "passive"))
    )
    (net (code "64") (name "Net-(IC9-Pad14)") (class "Default")
      (node (ref "IC9") (pin "14") (pinfunction "14_14") (pintype "passive"))
      (node (ref "IC9") (pin "15") (pinfunction "15_15") (pintype "passive"))
      (node (ref "R18") (pin "2") (pinfunction "2_2") (pintype "passive"))
    )
    (net (code "65") (name "Net-(IC10-Pad9)") (class "Default")
      (node (ref "IC10") (pin "9") (pinfunction "9_9") (pintype "passive"))
      (node (ref "IC9") (pin "10") (pinfunction "10_10") (pintype "passive"))
    )
    (net (code "66") (name "Net-(IC10-Pad10)") (class "Default")
      (node (ref "IC10") (pin "10") (pinfunction "10_10") (pintype "passive"))
      (node (ref "IC11") (pin "9") (pinfunction "9_9") (pintype "passive"))
    )
    (net (code "67") (name "Net-(IC10-Pad14)") (class "Default")
      (node (ref "IC10") (pin "14") (pinfunction "14_14") (pintype "passive"))
      (node (ref "IC10") (pin "15") (pinfunction "15_15") (pintype "passive"))
      (node (ref "R21") (pin "2") (pinfunction "2_2") (pintype "passive"))
    )
    (net (code "68") (name "Net-(IC11-Pad14)") (class "Default")
      (node (ref "IC11") (pin "14") (pinfunction "14_14") (pintype "passive"))
      (node (ref "IC11") (pin "15") (pinfunction "15_15") (pintype "passive"))
      (node (ref "R24") (pin "2") (pinfunction "2_2") (pintype "passive"))
    )
    (net (code "69") (name "Net-(LATCH-3)") (class "Default")
      (node (ref "IC1") (pin "7") (pinfunction "7_7") (pintype "passive"))
      (node (ref "IC10") (pin "7") (pinfunction "7_7") (pintype "passive"))
      (node (ref "IC11") (pin "7") (pinfunction "7_7") (pintype "passive"))
      (node (ref "IC2") (pin "7") (pinfunction "7_7") (pintype "passive"))
      (node (ref "IC3") (pin "7") (pinfunction "7_7") (pintype "passive"))
      (node (ref "IC6") (pin "7") (pinfunction "7_7") (pintype "passive"))
      (node (ref "IC7") (pin "7") (pinfunction "7_7") (pintype "passive"))
      (node (ref "IC9") (pin "7") (pinfunction "7_7") (pintype "passive"))
      (node (ref "LATCH") (pin "1") (pinfunction "3_1") (pintype "passive"))
    )
    (net (code "70") (name "unconnected-(IC1-Pad1)") (class "Default")
      (node (ref "IC1") (pin "1") (pinfunction "1_1") (pintype "passive"))
    )
    (net (code "71") (name "unconnected-(IC1-Pad3)") (class "Default")
      (node (ref "IC1") (pin "3") (pinfunction "3_3") (pintype "passive"))
    )
    (net (code "72") (name "unconnected-(IC1-Pad12)") (class "Default")
      (node (ref "IC1") (pin "12") (pinfunction "12_12") (pintype "passive"))
    )
    (net (code "73") (name "unconnected-(IC1-Pad13)") (class "Default")
      (node (ref "IC1") (pin "13") (pinfunction "13_13") (pintype "passive"))
    )
    (net (code "74") (name "unconnected-(IC1-Pad16)") (class "Default")
      (node (ref "IC1") (pin "16") (pinfunction "16_16") (pintype "passive"))
    )
    (net (code "75") (name "unconnected-(IC1-Pad18)") (class "Default")
      (node (ref "IC1") (pin "18") (pinfunction "18_18") (pintype "passive"))
    )
    (net (code "76") (name "unconnected-(IC1-Pad19)") (class "Default")
      (node (ref "IC1") (pin "19") (pinfunction "19_19") (pintype "passive"))
    )
    (net (code "77") (name "unconnected-(IC1-Pad22)") (class "Default")
      (node (ref "IC1") (pin "22") (pinfunction "22_22") (pintype "passive"))
    )
    (net (code "78") (name "unconnected-(IC1-Pad24)") (class "Default")
      (node (ref "IC1") (pin "24") (pinfunction "24_24") (pintype "passive"))
    )
    (net (code "79") (name "unconnected-(IC2-Pad1)") (class "Default")
      (node (ref "IC2") (pin "1") (pinfunction "1_1") (pintype "passive"))
    )
    (net (code "80") (name "unconnected-(IC2-Pad3)") (class "Default")
      (node (ref "IC2") (pin "3") (pinfunction "3_3") (pintype "passive"))
    )
    (net (code "81") (name "unconnected-(IC2-Pad12)") (class "Default")
      (node (ref "IC2") (pin "12") (pinfunction "12_12") (pintype "passive"))
    )
    (net (code "82") (name "unconnected-(IC2-Pad13)") (class "Default")
      (node (ref "IC2") (pin "13") (pinfunction "13_13") (pintype "passive"))
    )
    (net (code "83") (name "unconnected-(IC2-Pad16)") (class "Default")
      (node (ref "IC2") (pin "16") (pinfunction "16_16") (pintype "passive"))
    )
    (net (code "84") (name "unconnected-(IC2-Pad18)") (class "Default")
      (node (ref "IC2") (pin "18") (pinfunction "18_18") (pintype "passive"))
    )
    (net (code "85") (name "unconnected-(IC2-Pad19)") (class "Default")
      (node (ref "IC2") (pin "19") (pinfunction "19_19") (pintype "passive"))
    )
    (net (code "86") (name "unconnected-(IC2-Pad22)") (class "Default")
      (node (ref "IC2") (pin "22") (pinfunction "22_22") (pintype "passive"))
    )
    (net (code "87") (name "unconnected-(IC2-Pad24)") (class "Default")
      (node (ref "IC2") (pin "24") (pinfunction "24_24") (pintype "passive"))
    )
    (net (code "88") (name "unconnected-(IC3-Pad1)") (class "Default")
      (node (ref "IC3") (pin "1") (pinfunction "1_1") (pintype "passive"))
    )
    (net (code "89") (name "unconnected-(IC3-Pad3)") (class "Default")
      (node (ref "IC3") (pin "3") (pinfunction "3_3") (pintype "passive"))
    )
    (net (code "90") (name "unconnected-(IC3-Pad12)") (class "Default")
      (node (ref "IC3") (pin "12") (pinfunction "12_12") (pintype "passive"))
    )
    (net (code "91") (name "unconnected-(IC3-Pad13)") (class "Default")
      (node (ref "IC3") (pin "13") (pinfunction "13_13") (pintype "passive"))
    )
    (net (code "92") (name "unconnected-(IC3-Pad16)") (class "Default")
      (node (ref "IC3") (pin "16") (pinfunction "16_16") (pintype "passive"))
    )
    (net (code "93") (name "unconnected-(IC3-Pad18)") (class "Default")
      (node (ref "IC3") (pin "18") (pinfunction "18_18") (pintype "passive"))
    )
    (net (code "94") (name "unconnected-(IC3-Pad19)") (class "Default")
      (node (ref "IC3") (pin "19") (pinfunction "19_19") (pintype "passive"))
    )
    (net (code "95") (name "unconnected-(IC3-Pad22)") (class "Default")
      (node (ref "IC3") (pin "22") (pinfunction "22_22") (pintype "passive"))
    )
    (net (code "96") (name "unconnected-(IC3-Pad24)") (class "Default")
      (node (ref "IC3") (pin "24") (pinfunction "24_24") (pintype "passive"))
    )
    (net (code "97") (name "unconnected-(IC6-Pad1)") (class "Default")
      (node (ref "IC6") (pin "1") (pinfunction "1_1") (pintype "passive"))
    )
    (net (code "98") (name "unconnected-(IC6-Pad3)") (class "Default")
      (node (ref "IC6") (pin "3") (pinfunction "3_3") (pintype "passive"))
    )
    (net (code "99") (name "unconnected-(IC6-Pad12)") (class "Default")
      (node (ref "IC6") (pin "12") (pinfunction "12_12") (pintype "passive"))
    )
    (net (code "100") (name "unconnected-(IC6-Pad13)") (class "Default")
      (node (ref "IC6") (pin "13") (pinfunction "13_13") (pintype "passive"))
    )
    (net (code "101") (name "unconnected-(IC6-Pad16)") (class "Default")
      (node (ref "IC6") (pin "16") (pinfunction "16_16") (pintype "passive"))
    )
    (net (code "102") (name "unconnected-(IC6-Pad18)") (class "Default")
      (node (ref "IC6") (pin "18") (pinfunction "18_18") (pintype "passive"))
    )
    (net (code "103") (name "unconnected-(IC6-Pad19)") (class "Default")
      (node (ref "IC6") (pin "19") (pinfunction "19_19") (pintype "passive"))
    )
    (net (code "104") (name "unconnected-(IC6-Pad22)") (class "Default")
      (node (ref "IC6") (pin "22") (pinfunction "22_22") (pintype "passive"))
    )
    (net (code "105") (name "unconnected-(IC6-Pad24)") (class "Default")
      (node (ref "IC6") (pin "24") (pinfunction "24_24") (pintype "passive"))
    )
    (net (code "106") (name "unconnected-(IC7-Pad1)") (class "Default")
      (node (ref "IC7") (pin "1") (pinfunction "1_1") (pintype "passive"))
    )
    (net (code "107") (name "unconnected-(IC7-Pad3)") (class "Default")
      (node (ref "IC7") (pin "3") (pinfunction "3_3") (pintype "passive"))
    )
    (net (code "108") (name "unconnected-(IC7-Pad12)") (class "Default")
      (node (ref "IC7") (pin "12") (pinfunction "12_12") (pintype "passive"))
    )
    (net (code "109") (name "unconnected-(IC7-Pad13)") (class "Default")
      (node (ref "IC7") (pin "13") (pinfunction "13_13") (pintype "passive"))
    )
    (net (code "110") (name "unconnected-(IC7-Pad16)") (class "Default")
      (node (ref "IC7") (pin "16") (pinfunction "16_16") (pintype "passive"))
    )
    (net (code "111") (name "unconnected-(IC7-Pad18)") (class "Default")
      (node (ref "IC7") (pin "18") (pinfunction "18_18") (pintype "passive"))
    )
    (net (code "112") (name "unconnected-(IC7-Pad19)") (class "Default")
      (node (ref "IC7") (pin "19") (pinfunction "19_19") (pintype "passive"))
    )
    (net (code "113") (name "unconnected-(IC7-Pad22)") (class "Default")
      (node (ref "IC7") (pin "22") (pinfunction "22_22") (pintype "passive"))
    )
    (net (code "114") (name "unconnected-(IC7-Pad24)") (class "Default")
      (node (ref "IC7") (pin "24") (pinfunction "24_24") (pintype "passive"))
    )
    (net (code "115") (name "unconnected-(IC9-Pad1)") (class "Default")
      (node (ref "IC9") (pin "1") (pinfunction "1_1") (pintype "passive"))
    )
    (net (code "116") (name "unconnected-(IC9-Pad3)") (class "Default")
      (node (ref "IC9") (pin "3") (pinfunction "3_3") (pintype "passive"))
    )
    (net (code "117") (name "unconnected-(IC9-Pad12)") (class "Default")
      (node (ref "IC9") (pin "12") (pinfunction "12_12") (pintype "passive"))
    )
    (net (code "118") (name "unconnected-(IC9-Pad13)") (class "Default")
      (node (ref "IC9") (pin "13") (pinfunction "13_13") (pintype "passive"))
    )
    (net (code "119") (name "unconnected-(IC9-Pad16)") (class "Default")
      (node (ref "IC9") (pin "16") (pinfunction "16_16") (pintype "passive"))
    )
    (net (code "120") (name "unconnected-(IC9-Pad18)") (class "Default")
      (node (ref "IC9") (pin "18") (pinfunction "18_18") (pintype "passive"))
    )
    (net (code "121") (name "unconnected-(IC9-Pad19)") (class "Default")
      (node (ref "IC9") (pin "19") (pinfunction "19_19") (pintype "passive"))
    )
    (net (code "122") (name "unconnected-(IC9-Pad22)") (class "Default")
      (node (ref "IC9") (pin "22") (pinfunction "22_22") (pintype "passive"))
    )
    (net (code "123") (name "unconnected-(IC9-Pad24)") (class "Default")
      (node (ref "IC9") (pin "24") (pinfunction "24_24") (pintype "passive"))
    )
    (net (code "124") (name "unconnected-(IC10-Pad1)") (class "Default")
      (node (ref "IC10") (pin "1") (pinfunction "1_1") (pintype "passive"))
    )
    (net (code "125") (name "unconnected-(IC10-Pad3)") (class "Default")
      (node (ref "IC10") (pin "3") (pinfunction "3_3") (pintype "passive"))
    )
    (net (code "126") (name "unconnected-(IC10-Pad12)") (class "Default")
      (node (ref "IC10") (pin "12") (pinfunction "12_12") (pintype "passive"))
    )
    (net (code "127") (name "unconnected-(IC10-Pad13)") (class "Default")
      (node (ref "IC10") (pin "13") (pinfunction "13_13") (pintype "passive"))
    )
    (net (code "128") (name "unconnected-(IC10-Pad16)") (class "Default")
      (node (ref "IC10") (pin "16") (pinfunction "16_16") (pintype "passive"))
    )
    (net (code "129") (name "unconnected-(IC10-Pad18)") (class "Default")
      (node (ref "IC10") (pin "18") (pinfunction "18_18") (pintype "passive"))
    )
    (net (code "130") (name "unconnected-(IC10-Pad19)") (class "Default")
      (node (ref "IC10") (pin "19") (pinfunction "19_19") (pintype "passive"))
    )
    (net (code "131") (name "unconnected-(IC10-Pad22)") (class "Default")
      (node (ref "IC10") (pin "22") (pinfunction "22_22") (pintype "passive"))
    )
    (net (code "132") (name "unconnected-(IC10-Pad24)") (class "Default")
      (node (ref "IC10") (pin "24") (pinfunction "24_24") (pintype "passive"))
    )
    (net (code "133") (name "unconnected-(IC11-Pad1)") (class "Default")
      (node (ref "IC11") (pin "1") (pinfunction "1_1") (pintype "passive"))
    )
    (net (code "134") (name "unconnected-(IC11-Pad3)") (class "Default")
      (node (ref "IC11") (pin "3") (pinfunction "3_3") (pintype "passive"))
    )
    (net (code "135") (name "unconnected-(IC11-Pad10)") (class "Default")
      (node (ref "IC11") (pin "10") (pinfunction "10_10") (pintype "passive"))
    )
    (net (code "136") (name "unconnected-(IC11-Pad12)") (class "Default")
      (node (ref "IC11") (pin "12") (pinfunction "12_12") (pintype "passive"))
    )
    (net (code "137") (name "unconnected-(IC11-Pad13)") (class "Default")
      (node (ref "IC11") (pin "13") (pinfunction "13_13") (pintype "passive"))
    )
    (net (code "138") (name "unconnected-(IC11-Pad16)") (class "Default")
      (node (ref "IC11") (pin "16") (pinfunction "16_16") (pintype "passive"))
    )
    (net (code "139") (name "unconnected-(IC11-Pad18)") (class "Default")
      (node (ref "IC11") (pin "18") (pinfunction "18_18") (pintype "passive"))
    )
    (net (code "140") (name "unconnected-(IC11-Pad19)") (class "Default")
      (node (ref "IC11") (pin "19") (pinfunction "19_19") (pintype "passive"))
    )
    (net (code "141") (name "unconnected-(IC11-Pad22)") (class "Default")
      (node (ref "IC11") (pin "22") (pinfunction "22_22") (pintype "passive"))
    )
    (net (code "142") (name "unconnected-(IC11-Pad24)") (class "Default")
      (node (ref "IC11") (pin "24") (pinfunction "24_24") (pintype "passive"))
    )
  )
)
